# Hall_LDOs.net
KiCad netlist of a schematic drawn in Altium Designer
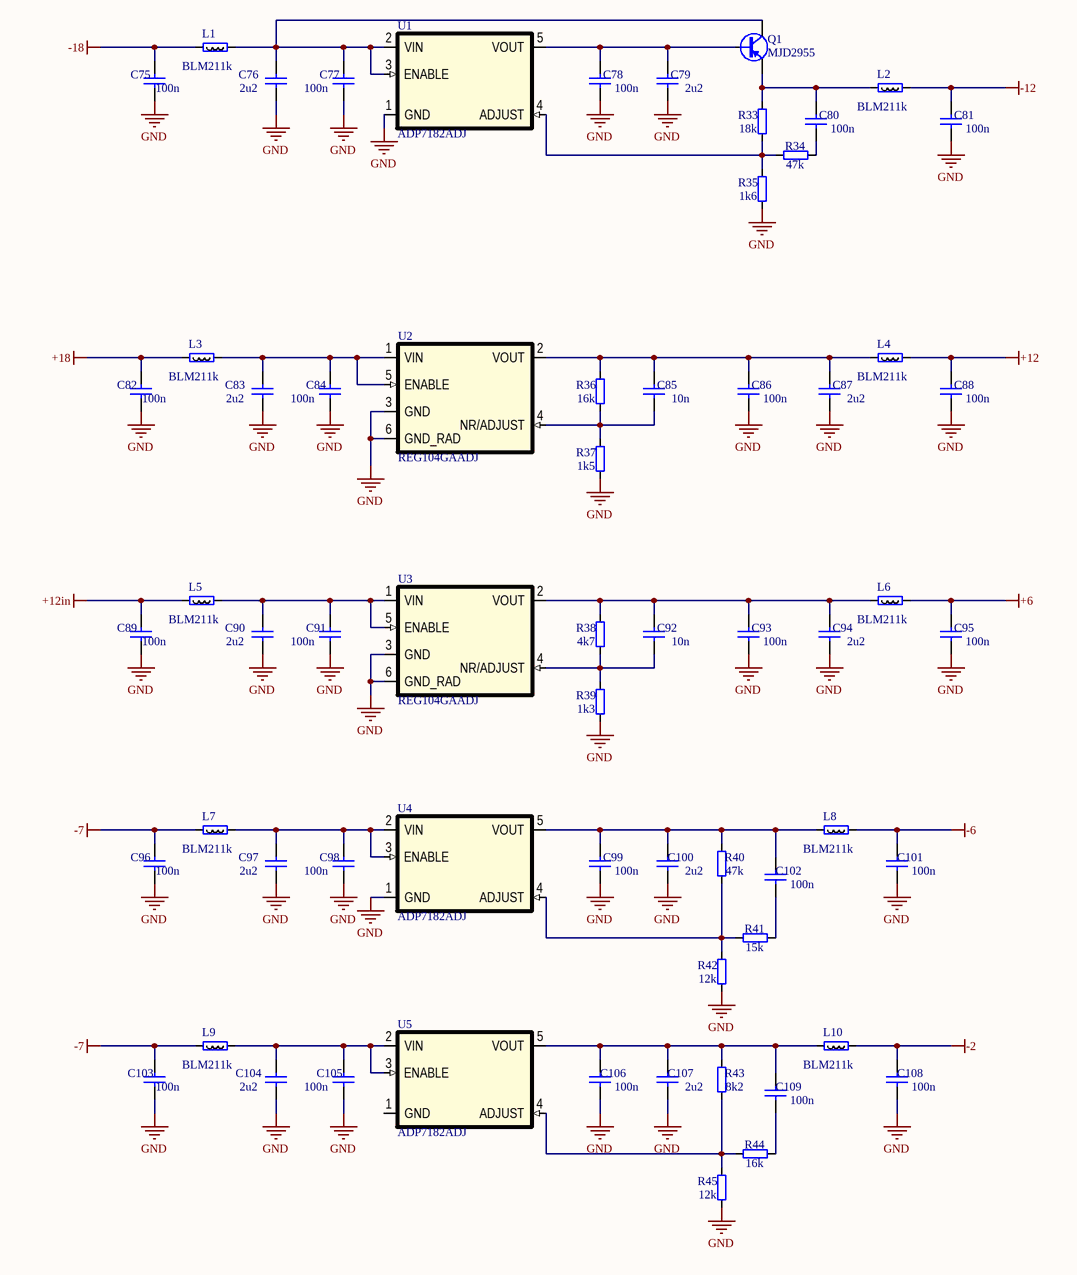
[diagram p0: Hall_LDOs.SchDoc]

(export (version "E")
  (design (tool "Eeschema 10.0.6"))
  (components
    (comp (ref "C75") (value "100n") (footprint "0603") (libsource (lib "Lib2408_Hall") (part "Capacitor")))
    (comp (ref "C76") (value "2u2") (footprint "0805") (libsource (lib "Lib2408_Hall") (part "Capacitor")))
    (comp (ref "C77") (value "100n") (footprint "0603") (libsource (lib "Lib2408_Hall") (part "Capacitor")))
    (comp (ref "C78") (value "100n") (footprint "0603") (libsource (lib "Lib2408_Hall") (part "Capacitor")))
    (comp (ref "C79") (value "2u2") (footprint "0805") (libsource (lib "Lib2408_Hall") (part "Capacitor")))
    (comp (ref "C80") (value "100n") (footprint "0603") (libsource (lib "Lib2408_Hall") (part "Capacitor")))
    (comp (ref "C81") (value "100n") (footprint "0603") (libsource (lib "Lib2408_Hall") (part "Capacitor")))
    (comp (ref "C82") (value "100n") (footprint "0603") (libsource (lib "Lib2408_Hall") (part "Capacitor")))
    (comp (ref "C83") (value "2u2") (footprint "0805") (libsource (lib "Lib2408_Hall") (part "Capacitor")))
    (comp (ref "C84") (value "100n") (footprint "0603") (libsource (lib "Lib2408_Hall") (part "Capacitor")))
    (comp (ref "C85") (value "10n") (footprint "0603") (libsource (lib "Lib2408_Hall") (part "Capacitor")))
    (comp (ref "C86") (value "100n") (footprint "0603") (libsource (lib "Lib2408_Hall") (part "Capacitor")))
    (comp (ref "C87") (value "2u2") (footprint "0805") (libsource (lib "Lib2408_Hall") (part "Capacitor")))
    (comp (ref "C88") (value "100n") (footprint "0603") (libsource (lib "Lib2408_Hall") (part "Capacitor")))
    (comp (ref "C89") (value "100n") (footprint "0603") (libsource (lib "Lib2408_Hall") (part "Capacitor")))
    (comp (ref "C90") (value "2u2") (footprint "0805") (libsource (lib "Lib2408_Hall") (part "Capacitor")))
    (comp (ref "C91") (value "100n") (footprint "0603") (libsource (lib "Lib2408_Hall") (part "Capacitor")))
    (comp (ref "C92") (value "10n") (footprint "0603") (libsource (lib "Lib2408_Hall") (part "Capacitor")))
    (comp (ref "C93") (value "100n") (footprint "0603") (libsource (lib "Lib2408_Hall") (part "Capacitor")))
    (comp (ref "C94") (value "2u2") (footprint "0805") (libsource (lib "Lib2408_Hall") (part "Capacitor")))
    (comp (ref "C95") (value "100n") (footprint "0603") (libsource (lib "Lib2408_Hall") (part "Capacitor")))
    (comp (ref "C96") (value "100n") (footprint "0603") (libsource (lib "Lib2408_Hall") (part "Capacitor")))
    (comp (ref "C97") (value "2u2") (footprint "0805") (libsource (lib "Lib2408_Hall") (part "Capacitor")))
    (comp (ref "C98") (value "100n") (footprint "0603") (libsource (lib "Lib2408_Hall") (part "Capacitor")))
    (comp (ref "C99") (value "100n") (footprint "0603") (libsource (lib "Lib2408_Hall") (part "Capacitor")))
    (comp (ref "C100") (value "2u2") (footprint "0805") (libsource (lib "Lib2408_Hall") (part "Capacitor")))
    (comp (ref "C101") (value "100n") (footprint "0603") (libsource (lib "Lib2408_Hall") (part "Capacitor")))
    (comp (ref "C102") (value "100n") (footprint "0603") (libsource (lib "Lib2408_Hall") (part "Capacitor")))
    (comp (ref "C103") (value "100n") (footprint "0603") (libsource (lib "Lib2408_Hall") (part "Capacitor")))
    (comp (ref "C104") (value "2u2") (footprint "0805") (libsource (lib "Lib2408_Hall") (part "Capacitor")))
    (comp (ref "C105") (value "100n") (footprint "0603") (libsource (lib "Lib2408_Hall") (part "Capacitor")))
    (comp (ref "C106") (value "100n") (footprint "0603") (libsource (lib "Lib2408_Hall") (part "Capacitor")))
    (comp (ref "C107") (value "2u2") (footprint "0805") (libsource (lib "Lib2408_Hall") (part "Capacitor")))
    (comp (ref "C108") (value "100n") (footprint "0603") (libsource (lib "Lib2408_Hall") (part "Capacitor")))
    (comp (ref "C109") (value "100n") (footprint "0603") (libsource (lib "Lib2408_Hall") (part "Capacitor")))
    (comp (ref "L1")
      (value "BLM211k")
      (footprint "0805")
      (description "SMD Ferrite bead 0805")
      (libsource (lib "Lib2408_Hall") (part "BLM21"))
    )
    (comp (ref "L2")
      (value "BLM211k")
      (footprint "0805")
      (description "SMD Ferrite bead 0805")
      (libsource (lib "Lib2408_Hall") (part "BLM21"))
    )
    (comp (ref "L3")
      (value "BLM211k")
      (footprint "0805")
      (description "SMD Ferrite bead 0805")
      (libsource (lib "Lib2408_Hall") (part "BLM21"))
    )
    (comp (ref "L4")
      (value "BLM211k")
      (footprint "0805")
      (description "SMD Ferrite bead 0805")
      (libsource (lib "Lib2408_Hall") (part "BLM21"))
    )
    (comp (ref "L5")
      (value "BLM211k")
      (footprint "0805")
      (description "SMD Ferrite bead 0805")
      (libsource (lib "Lib2408_Hall") (part "BLM21"))
    )
    (comp (ref "L6")
      (value "BLM211k")
      (footprint "0805")
      (description "SMD Ferrite bead 0805")
      (libsource (lib "Lib2408_Hall") (part "BLM21"))
    )
    (comp (ref "L7")
      (value "BLM211k")
      (footprint "0805")
      (description "SMD Ferrite bead 0805")
      (libsource (lib "Lib2408_Hall") (part "BLM21"))
    )
    (comp (ref "L8")
      (value "BLM211k")
      (footprint "0805")
      (description "SMD Ferrite bead 0805")
      (libsource (lib "Lib2408_Hall") (part "BLM21"))
    )
    (comp (ref "L9")
      (value "BLM211k")
      (footprint "0805")
      (description "SMD Ferrite bead 0805")
      (libsource (lib "Lib2408_Hall") (part "BLM21"))
    )
    (comp (ref "L10")
      (value "BLM211k")
      (footprint "0805")
      (description "SMD Ferrite bead 0805")
      (libsource (lib "Lib2408_Hall") (part "BLM21"))
    )
    (comp (ref "Q1")
      (value "MJD2955")
      (footprint "DPAK")
      (description "PNP транзистор")
      (fields (field (name "VOLTAGE") "-60V"))
      (libsource (lib "Lib2408_Hall") (part "MJD2955"))
    )
    (comp (ref "R33") (value "18k") (footprint "0603") (libsource (lib "Lib2408_Hall") (part "Resistor")))
    (comp (ref "R34") (value "47k") (footprint "0603") (libsource (lib "Lib2408_Hall") (part "Resistor")))
    (comp (ref "R35") (value "1k6") (footprint "0603") (libsource (lib "Lib2408_Hall") (part "Resistor")))
    (comp (ref "R36") (value "16k") (footprint "0603") (libsource (lib "Lib2408_Hall") (part "Resistor")))
    (comp (ref "R37") (value "1k5") (footprint "0603") (libsource (lib "Lib2408_Hall") (part "Resistor")))
    (comp (ref "R38") (value "4k7") (footprint "0603") (libsource (lib "Lib2408_Hall") (part "Resistor")))
    (comp (ref "R39") (value "1k3") (footprint "0603") (libsource (lib "Lib2408_Hall") (part "Resistor")))
    (comp (ref "R40") (value "47k") (footprint "0603") (libsource (lib "Lib2408_Hall") (part "Resistor")))
    (comp (ref "R41") (value "15k") (footprint "0603") (libsource (lib "Lib2408_Hall") (part "Resistor")))
    (comp (ref "R42") (value "12k") (footprint "0603") (libsource (lib "Lib2408_Hall") (part "Resistor")))
    (comp (ref "R43") (value "8k2") (footprint "0603") (libsource (lib "Lib2408_Hall") (part "Resistor")))
    (comp (ref "R44") (value "16k") (footprint "0603") (libsource (lib "Lib2408_Hall") (part "Resistor")))
    (comp (ref "R45") (value "12k") (footprint "0603") (libsource (lib "Lib2408_Hall") (part "Resistor")))
    (comp (ref "U1")
      (value "ADP7182ADJ")
      (footprint "SOT23-5")
      (description "Negative LDO Linear stabilizer")
      (libsource (lib "Lib2408_Hall") (part "ADP7182"))
    )
    (comp (ref "U2")
      (value "REG104GAADJ")
      (footprint "SOT223_6-127")
      (description "Positive LDO Linear stabilizer")
      (fields (field (name "TOLERANCE") "+-2% Max"))
      (libsource (lib "Lib2408_Hall") (part "REG104GA"))
    )
    (comp (ref "U3")
      (value "REG104GAADJ")
      (footprint "SOT223_6-127")
      (description "Positive LDO Linear stabilizer")
      (fields (field (name "TOLERANCE") "+-2% Max"))
      (libsource (lib "Lib2408_Hall") (part "REG104GA"))
    )
    (comp (ref "U4")
      (value "ADP7182ADJ")
      (footprint "SOT23-5")
      (description "Negative LDO Linear stabilizer")
      (libsource (lib "Lib2408_Hall") (part "ADP7182"))
    )
    (comp (ref "U5")
      (value "ADP7182ADJ")
      (footprint "SOT23-5")
      (description "Negative LDO Linear stabilizer")
      (libsource (lib "Lib2408_Hall") (part "ADP7182"))
    )
  )
  (nets
    (net (code "1") (name "+6") (class "Default")
      (node (ref "C95") (pin "2") (pinfunction "2_2") (pintype "passive"))
      (node (ref "L6") (pin "2") (pinfunction "2_2") (pintype "passive"))
    )
    (net (code "2") (name "+12") (class "Default")
      (node (ref "C88") (pin "2") (pinfunction "2_2") (pintype "passive"))
      (node (ref "L4") (pin "2") (pinfunction "2_2") (pintype "passive"))
    )
    (net (code "3") (name "+12in") (class "Default")
      (node (ref "C89") (pin "2") (pinfunction "2_2") (pintype "passive"))
      (node (ref "L5") (pin "1") (pinfunction "1_1") (pintype "passive"))
    )
    (net (code "4") (name "+18") (class "Default")
      (node (ref "C82") (pin "2") (pinfunction "2_2") (pintype "passive"))
      (node (ref "L3") (pin "1") (pinfunction "1_1") (pintype "passive"))
    )
    (net (code "5") (name "-2") (class "Default")
      (node (ref "C108") (pin "2") (pinfunction "2_2") (pintype "passive"))
      (node (ref "L10") (pin "2") (pinfunction "2_2") (pintype "passive"))
    )
    (net (code "6") (name "-6") (class "Default")
      (node (ref "C101") (pin "2") (pinfunction "2_2") (pintype "passive"))
      (node (ref "L8") (pin "2") (pinfunction "2_2") (pintype "passive"))
    )
    (net (code "7") (name "-7") (class "Default")
      (node (ref "C103") (pin "2") (pinfunction "2_2") (pintype "passive"))
      (node (ref "C96") (pin "2") (pinfunction "2_2") (pintype "passive"))
      (node (ref "L7") (pin "1") (pinfunction "1_1") (pintype "passive"))
      (node (ref "L9") (pin "1") (pinfunction "1_1") (pintype "passive"))
    )
    (net (code "8") (name "-12") (class "Default")
      (node (ref "C81") (pin "2") (pinfunction "2_2") (pintype "passive"))
      (node (ref "L2") (pin "2") (pinfunction "2_2") (pintype "passive"))
    )
    (net (code "9") (name "-18") (class "Default")
      (node (ref "C75") (pin "2") (pinfunction "2_2") (pintype "passive"))
      (node (ref "L1") (pin "1") (pinfunction "1_1") (pintype "passive"))
    )
    (net (code "10") (name "GND") (class "Default")
      (node (ref "C100") (pin "1") (pinfunction "1_1") (pintype "passive"))
      (node (ref "C101") (pin "1") (pinfunction "1_1") (pintype "passive"))
      (node (ref "C103") (pin "1") (pinfunction "1_1") (pintype "passive"))
      (node (ref "C104") (pin "1") (pinfunction "1_1") (pintype "passive"))
      (node (ref "C105") (pin "1") (pinfunction "1_1") (pintype "passive"))
      (node (ref "C106") (pin "1") (pinfunction "1_1") (pintype "passive"))
      (node (ref "C107") (pin "1") (pinfunction "1_1") (pintype "passive"))
      (node (ref "C108") (pin "1") (pinfunction "1_1") (pintype "passive"))
      (node (ref "C75") (pin "1") (pinfunction "1_1") (pintype "passive"))
      (node (ref "C76") (pin "1") (pinfunction "1_1") (pintype "passive"))
      (node (ref "C77") (pin "1") (pinfunction "1_1") (pintype "passive"))
      (node (ref "C78") (pin "1") (pinfunction "1_1") (pintype "passive"))
      (node (ref "C79") (pin "1") (pinfunction "1_1") (pintype "passive"))
      (node (ref "C81") (pin "1") (pinfunction "1_1") (pintype "passive"))
      (node (ref "C82") (pin "1") (pinfunction "1_1") (pintype "passive"))
      (node (ref "C83") (pin "1") (pinfunction "1_1") (pintype "passive"))
      (node (ref "C84") (pin "1") (pinfunction "1_1") (pintype "passive"))
      (node (ref "C86") (pin "1") (pinfunction "1_1") (pintype "passive"))
      (node (ref "C87") (pin "1") (pinfunction "1_1") (pintype "passive"))
      (node (ref "C88") (pin "1") (pinfunction "1_1") (pintype "passive"))
      (node (ref "C89") (pin "1") (pinfunction "1_1") (pintype "passive"))
      (node (ref "C90") (pin "1") (pinfunction "1_1") (pintype "passive"))
      (node (ref "C91") (pin "1") (pinfunction "1_1") (pintype "passive"))
      (node (ref "C93") (pin "1") (pinfunction "1_1") (pintype "passive"))
      (node (ref "C94") (pin "1") (pinfunction "1_1") (pintype "passive"))
      (node (ref "C95") (pin "1") (pinfunction "1_1") (pintype "passive"))
      (node (ref "C96") (pin "1") (pinfunction "1_1") (pintype "passive"))
      (node (ref "C97") (pin "1") (pinfunction "1_1") (pintype "passive"))
      (node (ref "C98") (pin "1") (pinfunction "1_1") (pintype "passive"))
      (node (ref "C99") (pin "1") (pinfunction "1_1") (pintype "passive"))
      (node (ref "R35") (pin "1") (pinfunction "1_1") (pintype "passive"))
      (node (ref "R37") (pin "1") (pinfunction "1_1") (pintype "passive"))
      (node (ref "R39") (pin "1") (pinfunction "1_1") (pintype "passive"))
      (node (ref "R42") (pin "1") (pinfunction "1_1") (pintype "passive"))
      (node (ref "R45") (pin "1") (pinfunction "1_1") (pintype "passive"))
      (node (ref "U1") (pin "1") (pinfunction "GND_1") (pintype "power_in"))
      (node (ref "U2") (pin "3") (pinfunction "GND_3") (pintype "power_in"))
      (node (ref "U2") (pin "6") (pinfunction "GND_RAD_6") (pintype "power_in"))
      (node (ref "U3") (pin "3") (pinfunction "GND_3") (pintype "power_in"))
      (node (ref "U3") (pin "6") (pinfunction "GND_RAD_6") (pintype "power_in"))
      (node (ref "U4") (pin "1") (pinfunction "GND_1") (pintype "power_in"))
    )
    (net (code "11") (name "Net-(C80-Pad1)") (class "Default")
      (node (ref "C80") (pin "1") (pinfunction "1_1") (pintype "passive"))
      (node (ref "R34") (pin "2") (pinfunction "2_2") (pintype "passive"))
    )
    (net (code "12") (name "Net-(C102-Pad1)") (class "Default")
      (node (ref "C102") (pin "1") (pinfunction "1_1") (pintype "passive"))
      (node (ref "R41") (pin "2") (pinfunction "2_2") (pintype "passive"))
    )
    (net (code "13") (name "Net-(C109-Pad1)") (class "Default")
      (node (ref "C109") (pin "1") (pinfunction "1_1") (pintype "passive"))
      (node (ref "R44") (pin "2") (pinfunction "2_2") (pintype "passive"))
    )
    (net (code "14") (name "Net-(Q1-B)") (class "Default")
      (node (ref "C78") (pin "2") (pinfunction "2_2") (pintype "passive"))
      (node (ref "C79") (pin "2") (pinfunction "2_2") (pintype "passive"))
      (node (ref "Q1") (pin "1") (pinfunction "B_1") (pintype "passive"))
      (node (ref "U1") (pin "5") (pinfunction "VOUT_5") (pintype "power_in"))
    )
    (net (code "15") (name "Net-(Q1-C)") (class "Default")
      (node (ref "C76") (pin "2") (pinfunction "2_2") (pintype "passive"))
      (node (ref "C77") (pin "2") (pinfunction "2_2") (pintype "passive"))
      (node (ref "L1") (pin "2") (pinfunction "2_2") (pintype "passive"))
      (node (ref "Q1") (pin "3") (pinfunction "C_3") (pintype "passive"))
      (node (ref "U1") (pin "2") (pinfunction "VIN_2") (pintype "power_in"))
      (node (ref "U1") (pin "3") (pinfunction "ENABLE_3") (pintype "input"))
    )
    (net (code "16") (name "Net-(Q1-E)") (class "Default")
      (node (ref "C80") (pin "2") (pinfunction "2_2") (pintype "passive"))
      (node (ref "L2") (pin "1") (pinfunction "1_1") (pintype "passive"))
      (node (ref "Q1") (pin "2") (pinfunction "E_2") (pintype "passive"))
      (node (ref "R33") (pin "2") (pinfunction "2_2") (pintype "passive"))
    )
    (net (code "17") (name "Net-(U1-ADJUST)") (class "Default")
      (node (ref "R33") (pin "1") (pinfunction "1_1") (pintype "passive"))
      (node (ref "R34") (pin "1") (pinfunction "1_1") (pintype "passive"))
      (node (ref "R35") (pin "2") (pinfunction "2_2") (pintype "passive"))
      (node (ref "U1") (pin "4") (pinfunction "ADJUST_4") (pintype "input"))
    )
    (net (code "18") (name "Net-(U2-ENABLE)") (class "Default")
      (node (ref "C83") (pin "2") (pinfunction "2_2") (pintype "passive"))
      (node (ref "C84") (pin "2") (pinfunction "2_2") (pintype "passive"))
      (node (ref "L3") (pin "2") (pinfunction "2_2") (pintype "passive"))
      (node (ref "U2") (pin "1") (pinfunction "VIN_1") (pintype "power_in"))
      (node (ref "U2") (pin "5") (pinfunction "ENABLE_5") (pintype "input"))
    )
    (net (code "19") (name "Net-(U2-NR{slash}ADJUST)") (class "Default")
      (node (ref "C85") (pin "1") (pinfunction "1_1") (pintype "passive"))
      (node (ref "R36") (pin "1") (pinfunction "1_1") (pintype "passive"))
      (node (ref "R37") (pin "2") (pinfunction "2_2") (pintype "passive"))
      (node (ref "U2") (pin "4") (pinfunction "NR/ADJUST_4") (pintype "input"))
    )
    (net (code "20") (name "Net-(U2-VOUT)") (class "Default")
      (node (ref "C85") (pin "2") (pinfunction "2_2") (pintype "passive"))
      (node (ref "C86") (pin "2") (pinfunction "2_2") (pintype "passive"))
      (node (ref "C87") (pin "2") (pinfunction "2_2") (pintype "passive"))
      (node (ref "L4") (pin "1") (pinfunction "1_1") (pintype "passive"))
      (node (ref "R36") (pin "2") (pinfunction "2_2") (pintype "passive"))
      (node (ref "U2") (pin "2") (pinfunction "VOUT_2") (pintype "power_in"))
    )
    (net (code "21") (name "Net-(U3-ENABLE)") (class "Default")
      (node (ref "C90") (pin "2") (pinfunction "2_2") (pintype "passive"))
      (node (ref "C91") (pin "2") (pinfunction "2_2") (pintype "passive"))
      (node (ref "L5") (pin "2") (pinfunction "2_2") (pintype "passive"))
      (node (ref "U3") (pin "1") (pinfunction "VIN_1") (pintype "power_in"))
      (node (ref "U3") (pin "5") (pinfunction "ENABLE_5") (pintype "input"))
    )
    (net (code "22") (name "Net-(U3-NR{slash}ADJUST)") (class "Default")
      (node (ref "C92") (pin "1") (pinfunction "1_1") (pintype "passive"))
      (node (ref "R38") (pin "1") (pinfunction "1_1") (pintype "passive"))
      (node (ref "R39") (pin "2") (pinfunction "2_2") (pintype "passive"))
      (node (ref "U3") (pin "4") (pinfunction "NR/ADJUST_4") (pintype "input"))
    )
    (net (code "23") (name "Net-(U3-VOUT)") (class "Default")
      (node (ref "C92") (pin "2") (pinfunction "2_2") (pintype "passive"))
      (node (ref "C93") (pin "2") (pinfunction "2_2") (pintype "passive"))
      (node (ref "C94") (pin "2") (pinfunction "2_2") (pintype "passive"))
      (node (ref "L6") (pin "1") (pinfunction "1_1") (pintype "passive"))
      (node (ref "R38") (pin "2") (pinfunction "2_2") (pintype "passive"))
      (node (ref "U3") (pin "2") (pinfunction "VOUT_2") (pintype "power_in"))
    )
    (net (code "24") (name "Net-(U4-ADJUST)") (class "Default")
      (node (ref "R40") (pin "1") (pinfunction "1_1") (pintype "passive"))
      (node (ref "R41") (pin "1") (pinfunction "1_1") (pintype "passive"))
      (node (ref "R42") (pin "2") (pinfunction "2_2") (pintype "passive"))
      (node (ref "U4") (pin "4") (pinfunction "ADJUST_4") (pintype "input"))
    )
    (net (code "25") (name "Net-(U4-ENABLE)") (class "Default")
      (node (ref "C97") (pin "2") (pinfunction "2_2") (pintype "passive"))
      (node (ref "C98") (pin "2") (pinfunction "2_2") (pintype "passive"))
      (node (ref "L7") (pin "2") (pinfunction "2_2") (pintype "passive"))
      (node (ref "U4") (pin "2") (pinfunction "VIN_2") (pintype "power_in"))
      (node (ref "U4") (pin "3") (pinfunction "ENABLE_3") (pintype "input"))
    )
    (net (code "26") (name "Net-(U4-VOUT)") (class "Default")
      (node (ref "C100") (pin "2") (pinfunction "2_2") (pintype "passive"))
      (node (ref "C102") (pin "2") (pinfunction "2_2") (pintype "passive"))
      (node (ref "C99") (pin "2") (pinfunction "2_2") (pintype "passive"))
      (node (ref "L8") (pin "1") (pinfunction "1_1") (pintype "passive"))
      (node (ref "R40") (pin "2") (pinfunction "2_2") (pintype "passive"))
      (node (ref "U4") (pin "5") (pinfunction "VOUT_5") (pintype "power_in"))
    )
    (net (code "27") (name "Net-(U5-ADJUST)") (class "Default")
      (node (ref "R43") (pin "1") (pinfunction "1_1") (pintype "passive"))
      (node (ref "R44") (pin "1") (pinfunction "1_1") (pintype "passive"))
      (node (ref "R45") (pin "2") (pinfunction "2_2") (pintype "passive"))
      (node (ref "U5") (pin "4") (pinfunction "ADJUST_4") (pintype "input"))
    )
    (net (code "28") (name "Net-(U5-ENABLE)") (class "Default")
      (node (ref "C104") (pin "2") (pinfunction "2_2") (pintype "passive"))
      (node (ref "C105") (pin "2") (pinfunction "2_2") (pintype "passive"))
      (node (ref "L9") (pin "2") (pinfunction "2_2") (pintype "passive"))
      (node (ref "U5") (pin "2") (pinfunction "VIN_2") (pintype "power_in"))
      (node (ref "U5") (pin "3") (pinfunction "ENABLE_3") (pintype "input"))
    )
    (net (code "29") (name "Net-(U5-VOUT)") (class "Default")
      (node (ref "C106") (pin "2") (pinfunction "2_2") (pintype "passive"))
      (node (ref "C107") (pin "2") (pinfunction "2_2") (pintype "passive"))
      (node (ref "C109") (pin "2") (pinfunction "2_2") (pintype "passive"))
      (node (ref "L10") (pin "1") (pinfunction "1_1") (pintype "passive"))
      (node (ref "R43") (pin "2") (pinfunction "2_2") (pintype "passive"))
      (node (ref "U5") (pin "5") (pinfunction "VOUT_5") (pintype "power_in"))
    )
    (net (code "30") (name "unconnected-(U5-GND-Pad1)") (class "Default")
      (node (ref "U5") (pin "1") (pinfunction "GND_1") (pintype "power_in"))
    )
  )
)
